# Power.net
KiCad netlist of a schematic drawn in Altium Designer
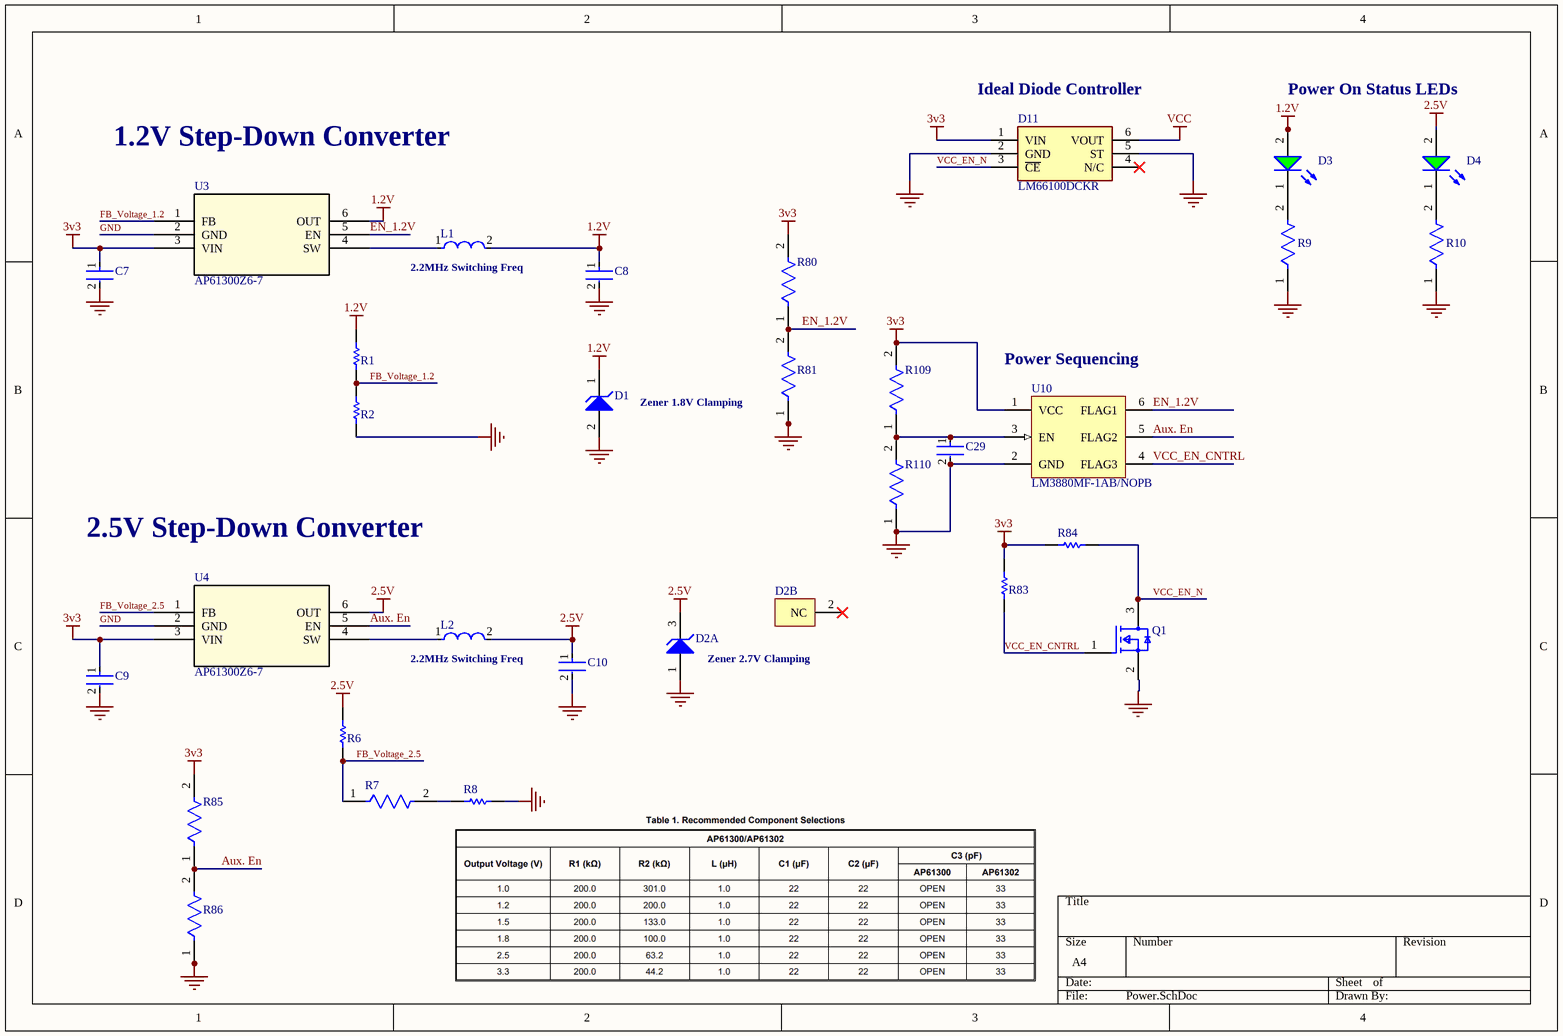
[diagram p0: Power.SchDoc]

(export (version "E")
  (design (tool "Eeschema 10.0.6"))
  (components
    (comp (ref "C7")
      (value "GRT21BR61E226ME13L")
      (footprint "FP-GRT21B-0_2-IPC_C")
      (description "Multi-Layer Ceramic Capacitor 22uF 25V X5R ±20% 0805 Emboss T/R")
      (fields (field (name "TOLERANCE") "20%"))
      (libsource (lib "Altium Content Vault") (part "02cd4be3c70576c341d710602a673aa"))
    )
    (comp (ref "C8")
      (value "GRT21BR61E226ME13L")
      (footprint "FP-GRT21B-0_2-IPC_C")
      (description "Multi-Layer Ceramic Capacitor 22uF 25V X5R ±20% 0805 Emboss T/R")
      (fields (field (name "TOLERANCE") "20%"))
      (libsource (lib "Altium Content Vault") (part "02cd4be3c70576c341d710602a673aa"))
    )
    (comp (ref "C9")
      (value "GRT21BR61E226ME13L")
      (footprint "FP-GRT21B-0_2-IPC_C")
      (description "Multi-Layer Ceramic Capacitor 22uF 25V X5R ±20% 0805 Emboss T/R")
      (fields (field (name "TOLERANCE") "20%"))
      (libsource (lib "Altium Content Vault") (part "02cd4be3c70576c341d710602a673aa"))
    )
    (comp (ref "C10")
      (value "GRT21BR61E226ME13L")
      (footprint "FP-GRT21B-0_2-IPC_C")
      (description "Multi-Layer Ceramic Capacitor 22uF 25V X5R ±20% 0805 Emboss T/R")
      (fields (field (name "TOLERANCE") "20%"))
      (libsource (lib "Altium Content Vault") (part "02cd4be3c70576c341d710602a673aa"))
    )
    (comp (ref "C29")
      (value "CC0402KRX7R7BB104")
      (footprint "FP-CC0402-MFG")
      (description "CAP CER 0.1UF 16V X7R 0402")
      (fields (field (name "MANUFACTURER") "YAGEO") (field (name "TOLERANCE") "0.1"))
      (libsource (lib "Altium Content Vault") (part "11868f565c42a9108669ba33697ecf6"))
    )
    (comp (ref "D1")
      (value "SZMMSZ4678T1G")
      (footprint "ONSC-SOD-123-2-425-04_V")
      (description "Zener Voltage Regulator, 500 mW, 2-Pin SOD-123, Pb-Free, Tape and Reel")
      (fields (field (name "MANUFACTURER") "On Semiconductor"))
      (libsource (lib "Altium Content Vault") (part "ONSC-K1A2-2"))
    )
    (comp (ref "D2")
      (value "MMBZ5223BLT1G")
      (footprint "ONSC-SOT-23-3-318-08_V")
      (description "Zener Voltage Regulator, 225 mW, 3-Pin SOT-23, Pb-Free, Tape and Reel")
      (fields (field (name "MANUFACTURER") "On Semiconductor"))
      (libsource (lib "Altium Content Vault") (part "ONSC-A1K3-3"))
    )
    (comp (ref "D3")
      (value "150060VS75000")
      (footprint "WL-SMCW_0603_150060xx75000")
      (description "WURTH ELEKTRONIK - 150060VS75000 - LED, Green, SMD, 0603, 30 mA, 2 V, 570 nm")
      (libsource (lib "Altium Content Vault") (part "LED_Green_2A-1K"))
    )
    (comp (ref "D4")
      (value "150060VS75000")
      (footprint "WL-SMCW_0603_150060xx75000")
      (description "WURTH ELEKTRONIK - 150060VS75000 - LED, Green, SMD, 0603, 30 mA, 2 V, 570 nm")
      (libsource (lib "Altium Content Vault") (part "LED_Green_2A-1K"))
    )
    (comp (ref "D11")
      (value "LM66100DCKR")
      (footprint "SOP80P1176X120-54N:SOP65P210X110-6N")
      (description "Diode")
      (fields (field (name "MOUSER PART NUMBER") "595-LM66100DCKR"))
      (libsource (lib "*") (part "LM66100DCKR"))
    )
    (comp (ref "L1")
      (value "MLP2012H2R2MT0S1")
      (footprint "FP-MLP2012M-IPC_C")
      (description "Shielded Multilayer Inductor 2.2uH ±20% 1000mA 195mΩ SMD 0805")
      (fields (field (name "TOLERANCE") "20%"))
      (libsource (lib "Altium Content Vault") (part "725321dda6339637d4d059423bc1c3c"))
    )
    (comp (ref "L2")
      (value "MLP2012H2R2MT0S1")
      (footprint "FP-MLP2012M-IPC_C")
      (description "Shielded Multilayer Inductor 2.2uH ±20% 1000mA 195mΩ SMD 0805")
      (fields (field (name "TOLERANCE") "20%"))
      (libsource (lib "Altium Content Vault") (part "725321dda6339637d4d059423bc1c3c"))
    )
    (comp (ref "Q1")
      (value "MMBF170LT1G")
      (footprint "FP-318-08-IPC_B")
      (description "MOSFET N-CH 60V 500MA SOT-23")
      (libsource (lib "Altium Content Vault") (part "0a9ea7c96deaaede766a5b531c28de0"))
    )
    (comp (ref "R1")
      (value "ERJ-2RKF2003X")
      (footprint "RESC1005X40X25NL05T05")
      (description "Chip Resistor, 200 KOhm, +/- 1%, 100 mW, -55 to 155 degC, 0402 (1005 Metric), RoHS, Tape and Reel")
      (fields (field (name "TOLERANCE") "1%") (field (name "MANUFACTURER") "Basic Passives"))
      (libsource (lib "Altium Content Vault") (part "RES-2"))
    )
    (comp (ref "R2")
      (value "RC0402FR-07100KL")
      (footprint "RESC1005X40X25NL05T10")
      (fields (field (name "MANUFACTURER") "Yageo / Phycomp"))
      (libsource (lib "Altium Content Vault") (part "RES"))
    )
    (comp (ref "R6")
      (value "ERJ-2RKF2003X")
      (footprint "RESC1005X40X25NL05T05")
      (description "Chip Resistor, 200 KOhm, +/- 1%, 100 mW, -55 to 155 degC, 0402 (1005 Metric), RoHS, Tape and Reel")
      (fields (field (name "TOLERANCE") "1%") (field (name "MANUFACTURER") "Basic Passives"))
      (libsource (lib "Altium Content Vault") (part "RES-2"))
    )
    (comp (ref "R7")
      (value "RT0603BRD0750KL")
      (footprint "FP-RT0603-0_55-MFG")
      (description "RES 50K OHM 0.1% 1/10W 0603")
      (libsource (lib "Altium Content Vault") (part "1029c3af85768c4190bb7ad29bc67b5"))
    )
    (comp (ref "R8")
      (value "RC0603FR-0713KL")
      (footprint "RESC1608X55X25LL10T15")
      (description "Chip Resistor, 13 KOhm, +/- 1%, 0.1 W, -55 to 155 degC, 0603 (1608 Metric), RoHS, Tape and Reel")
      (fields (field (name "TOLERANCE") "1%") (field (name "MANUFACTURER") "Yageo"))
      (libsource (lib "Altium Content Vault") (part "RES-2"))
    )
    (comp (ref "R9")
      (value "RC0603FR-0710KL")
      (footprint "FP-RC0603-0_55-IPC_C")
      (description "RES 10K OHM 1% 1/10W 0603")
      (fields (field (name "TOLERANCE") "1%"))
      (libsource (lib "Altium Content Vault") (part "1029c3af85768c4190bb7ad29bc67b5"))
    )
    (comp (ref "R10")
      (value "RC0603FR-0710KL")
      (footprint "FP-RC0603-0_55-IPC_C")
      (description "RES 10K OHM 1% 1/10W 0603")
      (fields (field (name "TOLERANCE") "1%"))
      (libsource (lib "Altium Content Vault") (part "1029c3af85768c4190bb7ad29bc67b5"))
    )
    (comp (ref "R80")
      (value "RC0603FR-07100KL")
      (footprint "FP-RC0603-0_55-MFG")
      (description "RES SMD 100K OHM 1% 1/10W 0603")
      (fields (field (name "TOLERANCE") "1%"))
      (libsource (lib "Altium Content Vault") (part "1029c3af85768c4190bb7ad29bc67b5"))
    )
    (comp (ref "R81")
      (value "RT0805BRD07200KL")
      (footprint "FP-RT0805-MFG")
      (description "RES SMD 200K OHM 0.1% 1/8W 0805")
      (fields
        (field (name "MANUFACTURER") "Yageo")
        (field (name "OCTOPART") "https://octopart.com/rt0805brd07200kl-yageo-1477199")
      )
      (libsource (lib "Altium Content Vault") (part "1029c3af85768c4190bb7ad29bc67b5"))
    )
    (comp (ref "R83")
      (value "RC0402FR-0710KL")
      (footprint "RESC1005X40X25LL05T10")
      (fields (field (name "MANUFACTURER") "Yageo / Phycomp"))
      (libsource (lib "Altium Content Vault") (part "RES"))
    )
    (comp (ref "R84")
      (value "RC0402FR-0710KL")
      (footprint "RESC1005X40X25LL05T10")
      (fields (field (name "MANUFACTURER") "Yageo / Phycomp"))
      (libsource (lib "Altium Content Vault") (part "RES"))
    )
    (comp (ref "R85")
      (value "RC0603FR-07100KL")
      (footprint "FP-RC0603-0_55-MFG")
      (description "RES SMD 100K OHM 1% 1/10W 0603")
      (fields (field (name "TOLERANCE") "1%"))
      (libsource (lib "Altium Content Vault") (part "1029c3af85768c4190bb7ad29bc67b5"))
    )
    (comp (ref "R86")
      (value "RT0805BRD07200KL")
      (footprint "FP-RT0805-MFG")
      (description "RES SMD 200K OHM 0.1% 1/8W 0805")
      (fields
        (field (name "MANUFACTURER") "Yageo")
        (field (name "OCTOPART") "https://octopart.com/rt0805brd07200kl-yageo-1477199")
      )
      (libsource (lib "Altium Content Vault") (part "1029c3af85768c4190bb7ad29bc67b5"))
    )
    (comp (ref "R109")
      (value "RC0603FR-07100KL")
      (footprint "FP-RC0603-0_55-MFG")
      (description "RES SMD 100K OHM 1% 1/10W 0603")
      (fields (field (name "TOLERANCE") "1%"))
      (libsource (lib "Altium Content Vault") (part "1029c3af85768c4190bb7ad29bc67b5"))
    )
    (comp (ref "R110")
      (value "RC0603FR-07100KL")
      (footprint "FP-RC0603-0_55-MFG")
      (description "RES SMD 100K OHM 1% 1/10W 0603")
      (fields (field (name "TOLERANCE") "1%"))
      (libsource (lib "Altium Content Vault") (part "1029c3af85768c4190bb7ad29bc67b5"))
    )
    (comp (ref "U3")
      (value "AP61300Z6-7")
      (footprint "AP61300Z6-7_DIO")
      (description "No Description Available")
      (fields (field (name "COPYRIGHT") "Copyright (C) 2025 Ultra Librarian. All rights reserved."))
      (libsource (lib "AP61300Z6-7") (part "AP61300Z6-7"))
    )
    (comp (ref "U4")
      (value "AP61300Z6-7")
      (footprint "AP61300Z6-7_DIO")
      (description "No Description Available")
      (fields (field (name "COPYRIGHT") "Copyright (C) 2025 Ultra Librarian. All rights reserved."))
      (libsource (lib "AP61300Z6-7") (part "AP61300Z6-7"))
    )
    (comp (ref "U10")
      (value "LM3880MF-1AB/NOPB")
      (footprint "DBV0006A_M")
      (description "Power Sequencer, 6-pin SOT-23, Pb-Free, 1000 Reel")
      (fields (field (name "MANUFACTURER") "Texas Instruments"))
      (libsource (lib "Altium Content Vault") (part "PM-CNTL-LM3880-6"))
    )
  )
  (nets
    (net (code "1") (name "/Aux. En") (class "Default")
      (node (ref "R85") (pin "1") (pinfunction "1_1") (pintype "passive"))
      (node (ref "R86") (pin "2") (pinfunction "2_2") (pintype "passive"))
      (node (ref "U10") (pin "5") (pinfunction "FLAG2_5") (pintype "open_collector"))
      (node (ref "U4") (pin "5") (pinfunction "EN_5") (pintype "passive"))
    )
    (net (code "2") (name "/EN_1.2V") (class "Default")
      (node (ref "R80") (pin "1") (pinfunction "1_1") (pintype "passive"))
      (node (ref "R81") (pin "2") (pinfunction "2_2") (pintype "passive"))
      (node (ref "U10") (pin "6") (pinfunction "FLAG1_6") (pintype "open_collector"))
      (node (ref "U3") (pin "5") (pinfunction "EN_5") (pintype "passive"))
    )
    (net (code "3") (name "/FB_Voltage_1.2") (class "Default")
      (node (ref "R1") (pin "2") (pinfunction "2_2") (pintype "passive"))
      (node (ref "R2") (pin "1") (pinfunction "1_1") (pintype "passive"))
      (node (ref "U3") (pin "1") (pinfunction "FB_1") (pintype "passive"))
    )
    (net (code "4") (name "/FB_Voltage_2.5") (class "Default")
      (node (ref "R6") (pin "2") (pinfunction "2_2") (pintype "passive"))
      (node (ref "R7") (pin "1") (pinfunction "1_1") (pintype "passive"))
      (node (ref "U4") (pin "1") (pinfunction "FB_1") (pintype "passive"))
    )
    (net (code "5") (name "/VCC_EN_CNTRL") (class "Default")
      (node (ref "Q1") (pin "1") (pinfunction "G_1") (pintype "passive"))
      (node (ref "R83") (pin "1") (pinfunction "1_1") (pintype "passive"))
      (node (ref "U10") (pin "4") (pinfunction "FLAG3_4") (pintype "open_collector"))
    )
    (net (code "6") (name "/VCC_EN_N") (class "Default")
      (node (ref "D11") (pin "3") (pinfunction "~{CE}_3") (pintype "passive"))
      (node (ref "Q1") (pin "3") (pinfunction "D_3") (pintype "passive"))
      (node (ref "R84") (pin "2") (pinfunction "2_2") (pintype "passive"))
    )
    (net (code "7") (name "1.2V") (class "Default")
      (node (ref "C8") (pin "1") (pinfunction "1_1") (pintype "passive"))
      (node (ref "D1") (pin "1") (pinfunction "K_1") (pintype "passive"))
      (node (ref "D3") (pin "2") (pinfunction "A_2") (pintype "passive"))
      (node (ref "L1") (pin "2") (pinfunction "2_2") (pintype "passive"))
      (node (ref "R1") (pin "1") (pinfunction "1_1") (pintype "passive"))
      (node (ref "U3") (pin "6") (pinfunction "OUT_6") (pintype "passive"))
    )
    (net (code "8") (name "2.5V") (class "Default")
      (node (ref "C10") (pin "1") (pinfunction "1_1") (pintype "passive"))
      (node (ref "D2") (pin "3") (pinfunction "K_3") (pintype "passive"))
      (node (ref "D4") (pin "2") (pinfunction "A_2") (pintype "passive"))
      (node (ref "L2") (pin "2") (pinfunction "2_2") (pintype "passive"))
      (node (ref "R6") (pin "1") (pinfunction "1_1") (pintype "passive"))
      (node (ref "U4") (pin "6") (pinfunction "OUT_6") (pintype "passive"))
    )
    (net (code "9") (name "3v3") (class "Default")
      (node (ref "C7") (pin "1") (pinfunction "1_1") (pintype "passive"))
      (node (ref "C9") (pin "1") (pinfunction "1_1") (pintype "passive"))
      (node (ref "D11") (pin "1") (pinfunction "VIN_1") (pintype "passive"))
      (node (ref "R109") (pin "2") (pinfunction "2_2") (pintype "passive"))
      (node (ref "R80") (pin "2") (pinfunction "2_2") (pintype "passive"))
      (node (ref "R83") (pin "2") (pinfunction "2_2") (pintype "passive"))
      (node (ref "R84") (pin "1") (pinfunction "1_1") (pintype "passive"))
      (node (ref "R85") (pin "2") (pinfunction "2_2") (pintype "passive"))
      (node (ref "U10") (pin "1") (pinfunction "VCC_1") (pintype "power_in"))
      (node (ref "U3") (pin "3") (pinfunction "VIN_3") (pintype "passive"))
      (node (ref "U4") (pin "3") (pinfunction "VIN_3") (pintype "passive"))
    )
    (net (code "10") (name "GND") (class "Default")
      (node (ref "C10") (pin "2") (pinfunction "2_2") (pintype "passive"))
      (node (ref "C29") (pin "2") (pinfunction "2_2") (pintype "passive"))
      (node (ref "C7") (pin "2") (pinfunction "2_2") (pintype "passive"))
      (node (ref "C8") (pin "2") (pinfunction "2_2") (pintype "passive"))
      (node (ref "C9") (pin "2") (pinfunction "2_2") (pintype "passive"))
      (node (ref "D1") (pin "2") (pinfunction "A_2") (pintype "passive"))
      (node (ref "D11") (pin "2") (pinfunction "GND_2") (pintype "passive"))
      (node (ref "D11") (pin "5") (pinfunction "ST_5") (pintype "passive"))
      (node (ref "D2") (pin "1") (pinfunction "A_1") (pintype "passive"))
      (node (ref "R10") (pin "1") (pinfunction "1_1") (pintype "passive"))
      (node (ref "R110") (pin "1") (pinfunction "1_1") (pintype "passive"))
      (node (ref "R2") (pin "2") (pinfunction "2_2") (pintype "passive"))
      (node (ref "R8") (pin "2") (pinfunction "2_2") (pintype "passive"))
      (node (ref "R81") (pin "1") (pinfunction "1_1") (pintype "passive"))
      (node (ref "R86") (pin "1") (pinfunction "1_1") (pintype "passive"))
      (node (ref "R9") (pin "1") (pinfunction "1_1") (pintype "passive"))
      (node (ref "U10") (pin "2") (pinfunction "GND_2") (pintype "power_in"))
      (node (ref "U3") (pin "2") (pinfunction "GND_2") (pintype "passive"))
      (node (ref "U4") (pin "2") (pinfunction "GND_2") (pintype "passive"))
    )
    (net (code "11") (name "Net-(D3-K)") (class "Default")
      (node (ref "D3") (pin "1") (pinfunction "K_1") (pintype "passive"))
      (node (ref "R9") (pin "2") (pinfunction "2_2") (pintype "passive"))
    )
    (net (code "12") (name "Net-(D4-K)") (class "Default")
      (node (ref "D4") (pin "1") (pinfunction "K_1") (pintype "passive"))
      (node (ref "R10") (pin "2") (pinfunction "2_2") (pintype "passive"))
    )
    (net (code "13") (name "Net-(R7-Pad2)") (class "Default")
      (node (ref "R7") (pin "2") (pinfunction "2_2") (pintype "passive"))
      (node (ref "R8") (pin "1") (pinfunction "1_1") (pintype "passive"))
    )
    (net (code "14") (name "Net-(U3-SW)") (class "Default")
      (node (ref "L1") (pin "1") (pinfunction "1_1") (pintype "passive"))
      (node (ref "U3") (pin "4") (pinfunction "SW_4") (pintype "passive"))
    )
    (net (code "15") (name "Net-(U4-SW)") (class "Default")
      (node (ref "L2") (pin "1") (pinfunction "1_1") (pintype "passive"))
      (node (ref "U4") (pin "4") (pinfunction "SW_4") (pintype "passive"))
    )
    (net (code "16") (name "Net-(U10-EN)") (class "Default")
      (node (ref "C29") (pin "1") (pinfunction "1_1") (pintype "passive"))
      (node (ref "R109") (pin "1") (pinfunction "1_1") (pintype "passive"))
      (node (ref "R110") (pin "2") (pinfunction "2_2") (pintype "passive"))
      (node (ref "U10") (pin "3") (pinfunction "EN_3") (pintype "input"))
    )
    (net (code "17") (name "VCC") (class "Default")
      (node (ref "D11") (pin "6") (pinfunction "VOUT_6") (pintype "passive"))
    )
    (net (code "18") (name "unconnected-(D2B-NC-Pad2)") (class "Default")
      (node (ref "D2") (pin "2") (pinfunction "NC_2") (pintype "passive+no_connect"))
    )
    (net (code "19") (name "unconnected-(D11-N{slash}C-Pad4)") (class "Default")
      (node (ref "D11") (pin "4") (pinfunction "N/C_4") (pintype "passive+no_connect"))
    )
    (net (code "20") (name "unconnected-(Q1-S-Pad2)") (class "Default")
      (node (ref "Q1") (pin "2") (pinfunction "S_2") (pintype "passive"))
    )
  )
)
